# raspberryPi_sparkcore_interface.net
KiCad netlist of a schematic drawn in EAGLE
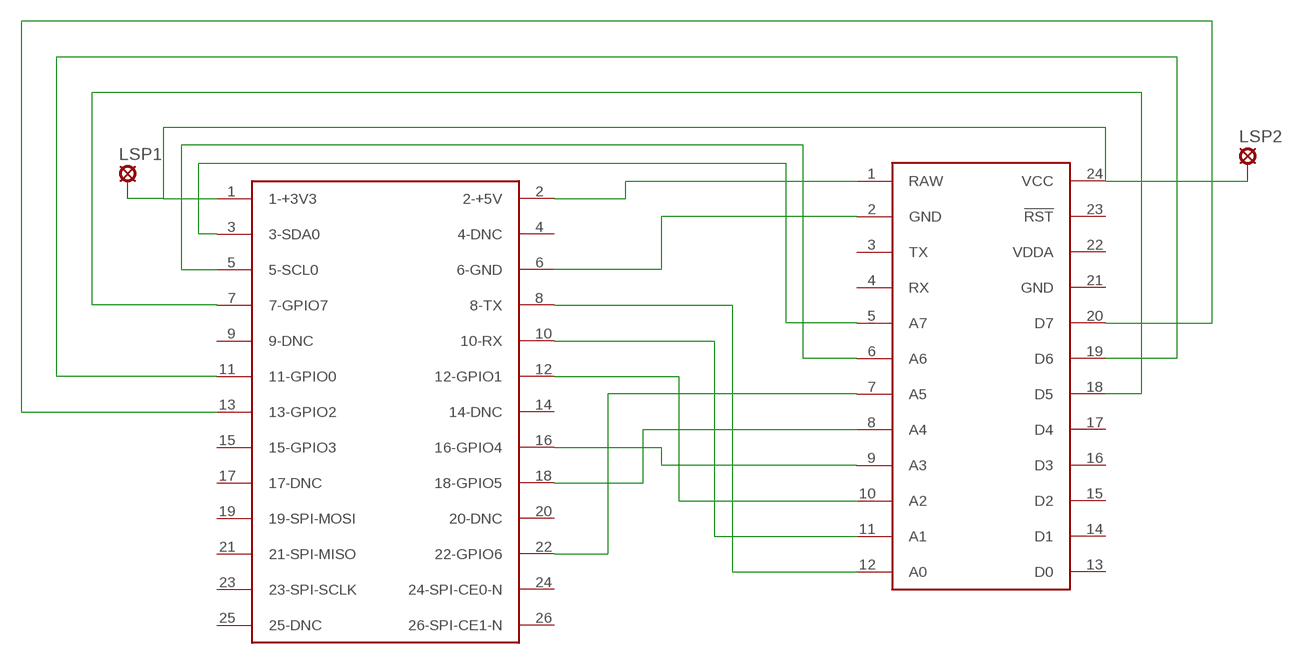
[diagram p0: schematic, sheet 1]

(export (version "E")
  (design (tool "Eeschema 10.0.6"))
  (components
    (comp (ref "LSP1")
      (value "MCS08")
      (footprint "eagle-import:MCS08")
      (libsource (lib "eagle-import") (part "MCS08"))
    )
    (comp (ref "LSP2")
      (value "MCS08")
      (footprint "eagle-import:MCS08")
      (libsource (lib "eagle-import") (part "MCS08"))
    )
    (comp (ref "U$1")
      (value "RASPBERRY-PI")
      (footprint "eagle-import:RASPBERRY-PI")
      (libsource (lib "eagle-import") (part "RASPBERRY-PI"))
    )
    (comp (ref "U$2")
      (value "SPARK_CORECORE")
      (footprint "eagle-import:SPARK_CORE")
      (libsource (lib "eagle-import") (part "SPARK_CORECORE"))
    )
  )
  (nets
    (net (code "1") (name "/GND") (class "Default")
      (node (ref "U$2") (pin "21") (pinfunction "GND_21") (pintype "power_in"))
    )
    (net (code "2") (name "/VDDA") (class "Default")
      (node (ref "U$2") (pin "22") (pinfunction "VDDA_22") (pintype "power_in"))
    )
    (net (code "3") (name "Net-(U$1-1-+3V3)") (class "Default")
      (node (ref "LSP1") (pin "MP") (pinfunction "MP_MP") (pintype "passive"))
      (node (ref "LSP2") (pin "MP") (pinfunction "MP_MP") (pintype "passive"))
      (node (ref "U$1") (pin "1") (pinfunction "1-+3V3_1") (pintype "bidirectional"))
      (node (ref "U$2") (pin "24") (pinfunction "VCC_24") (pintype "power_in"))
    )
    (net (code "4") (name "Net-(U$1-2-+5V)") (class "Default")
      (node (ref "U$1") (pin "2") (pinfunction "2-+5V_2") (pintype "bidirectional"))
      (node (ref "U$2") (pin "1") (pinfunction "RAW_1") (pintype "power_in"))
    )
    (net (code "5") (name "Net-(U$1-3-SDA0)") (class "Default")
      (node (ref "U$1") (pin "3") (pinfunction "3-SDA0_3") (pintype "bidirectional"))
      (node (ref "U$2") (pin "5") (pinfunction "A7_5") (pintype "bidirectional"))
    )
    (net (code "6") (name "Net-(U$1-5-SCL0)") (class "Default")
      (node (ref "U$1") (pin "5") (pinfunction "5-SCL0_5") (pintype "bidirectional"))
      (node (ref "U$2") (pin "6") (pinfunction "A6_6") (pintype "bidirectional"))
    )
    (net (code "7") (name "Net-(U$1-6-GND)") (class "Default")
      (node (ref "U$1") (pin "6") (pinfunction "6-GND_6") (pintype "bidirectional"))
      (node (ref "U$2") (pin "2") (pinfunction "GND_2") (pintype "power_in"))
    )
    (net (code "8") (name "Net-(U$1-7-GPIO7)") (class "Default")
      (node (ref "U$1") (pin "7") (pinfunction "7-GPIO7_7") (pintype "bidirectional"))
      (node (ref "U$2") (pin "18") (pinfunction "D5_18") (pintype "bidirectional"))
    )
    (net (code "9") (name "Net-(U$1-8-TX)") (class "Default")
      (node (ref "U$1") (pin "8") (pinfunction "8-TX_8") (pintype "bidirectional"))
      (node (ref "U$2") (pin "12") (pinfunction "A0_12") (pintype "bidirectional"))
    )
    (net (code "10") (name "Net-(U$1-10-RX)") (class "Default")
      (node (ref "U$1") (pin "10") (pinfunction "10-RX_10") (pintype "bidirectional"))
      (node (ref "U$2") (pin "11") (pinfunction "A1_11") (pintype "bidirectional"))
    )
    (net (code "11") (name "Net-(U$1-11-GPIO0)") (class "Default")
      (node (ref "U$1") (pin "11") (pinfunction "11-GPIO0_11") (pintype "bidirectional"))
      (node (ref "U$2") (pin "19") (pinfunction "D6_19") (pintype "bidirectional"))
    )
    (net (code "12") (name "Net-(U$1-12-GPIO1)") (class "Default")
      (node (ref "U$1") (pin "12") (pinfunction "12-GPIO1_12") (pintype "bidirectional"))
      (node (ref "U$2") (pin "10") (pinfunction "A2_10") (pintype "bidirectional"))
    )
    (net (code "13") (name "Net-(U$1-13-GPIO2)") (class "Default")
      (node (ref "U$1") (pin "13") (pinfunction "13-GPIO2_13") (pintype "bidirectional"))
      (node (ref "U$2") (pin "20") (pinfunction "D7_20") (pintype "bidirectional"))
    )
    (net (code "14") (name "Net-(U$1-16-GPIO4)") (class "Default")
      (node (ref "U$1") (pin "16") (pinfunction "16-GPIO4_16") (pintype "bidirectional"))
      (node (ref "U$2") (pin "9") (pinfunction "A3_9") (pintype "bidirectional"))
    )
    (net (code "15") (name "Net-(U$1-18-GPIO5)") (class "Default")
      (node (ref "U$1") (pin "18") (pinfunction "18-GPIO5_18") (pintype "bidirectional"))
      (node (ref "U$2") (pin "8") (pinfunction "A4_8") (pintype "bidirectional"))
    )
    (net (code "16") (name "Net-(U$1-22-GPIO6)") (class "Default")
      (node (ref "U$1") (pin "22") (pinfunction "22-GPIO6_22") (pintype "bidirectional"))
      (node (ref "U$2") (pin "7") (pinfunction "A5_7") (pintype "bidirectional"))
    )
    (net (code "17") (name "unconnected-(U$1-4-DNC-Pad4)") (class "Default")
      (node (ref "U$1") (pin "4") (pinfunction "4-DNC_4") (pintype "bidirectional"))
    )
    (net (code "18") (name "unconnected-(U$1-9-DNC-Pad9)") (class "Default")
      (node (ref "U$1") (pin "9") (pinfunction "9-DNC_9") (pintype "bidirectional"))
    )
    (net (code "19") (name "unconnected-(U$1-14-DNC-Pad14)") (class "Default")
      (node (ref "U$1") (pin "14") (pinfunction "14-DNC_14") (pintype "bidirectional"))
    )
    (net (code "20") (name "unconnected-(U$1-15-GPIO3-Pad15)") (class "Default")
      (node (ref "U$1") (pin "15") (pinfunction "15-GPIO3_15") (pintype "bidirectional"))
    )
    (net (code "21") (name "unconnected-(U$1-17-DNC-Pad17)") (class "Default")
      (node (ref "U$1") (pin "17") (pinfunction "17-DNC_17") (pintype "bidirectional"))
    )
    (net (code "22") (name "unconnected-(U$1-19-SPI-MOSI-Pad19)") (class "Default")
      (node (ref "U$1") (pin "19") (pinfunction "19-SPI-MOSI_19") (pintype "bidirectional"))
    )
    (net (code "23") (name "unconnected-(U$1-20-DNC-Pad20)") (class "Default")
      (node (ref "U$1") (pin "20") (pinfunction "20-DNC_20") (pintype "bidirectional"))
    )
    (net (code "24") (name "unconnected-(U$1-21-SPI-MISO-Pad21)") (class "Default")
      (node (ref "U$1") (pin "21") (pinfunction "21-SPI-MISO_21") (pintype "bidirectional"))
    )
    (net (code "25") (name "unconnected-(U$1-23-SPI-SCLK-Pad23)") (class "Default")
      (node (ref "U$1") (pin "23") (pinfunction "23-SPI-SCLK_23") (pintype "bidirectional"))
    )
    (net (code "26") (name "unconnected-(U$1-24-SPI-CE0-N-Pad24)") (class "Default")
      (node (ref "U$1") (pin "24") (pinfunction "24-SPI-CE0-N_24") (pintype "bidirectional"))
    )
    (net (code "27") (name "unconnected-(U$1-25-DNC-Pad25)") (class "Default")
      (node (ref "U$1") (pin "25") (pinfunction "25-DNC_25") (pintype "bidirectional"))
    )
    (net (code "28") (name "unconnected-(U$1-26-SPI-CE1-N-Pad26)") (class "Default")
      (node (ref "U$1") (pin "26") (pinfunction "26-SPI-CE1-N_26") (pintype "bidirectional"))
    )
    (net (code "29") (name "unconnected-(U$2-D0-Pad13)") (class "Default")
      (node (ref "U$2") (pin "13") (pinfunction "D0_13") (pintype "bidirectional"))
    )
    (net (code "30") (name "unconnected-(U$2-D1-Pad14)") (class "Default")
      (node (ref "U$2") (pin "14") (pinfunction "D1_14") (pintype "bidirectional"))
    )
    (net (code "31") (name "unconnected-(U$2-D2-Pad15)") (class "Default")
      (node (ref "U$2") (pin "15") (pinfunction "D2_15") (pintype "bidirectional"))
    )
    (net (code "32") (name "unconnected-(U$2-D3-Pad16)") (class "Default")
      (node (ref "U$2") (pin "16") (pinfunction "D3_16") (pintype "bidirectional"))
    )
    (net (code "33") (name "unconnected-(U$2-D4-Pad17)") (class "Default")
      (node (ref "U$2") (pin "17") (pinfunction "D4_17") (pintype "bidirectional"))
    )
    (net (code "34") (name "unconnected-(U$2-RX-Pad4)") (class "Default")
      (node (ref "U$2") (pin "4") (pinfunction "RX_4") (pintype "bidirectional"))
    )
    (net (code "35") (name "unconnected-(U$2-TX-Pad3)") (class "Default")
      (node (ref "U$2") (pin "3") (pinfunction "TX_3") (pintype "bidirectional"))
    )
    (net (code "36") (name "unconnected-(U$2-~{RST}-Pad23)") (class "Default")
      (node (ref "U$2") (pin "23") (pinfunction "~{RST}_23") (pintype "bidirectional"))
    )
  )
)
